# MDBU020.net
KiCad netlist of a schematic drawn in Altium Designer
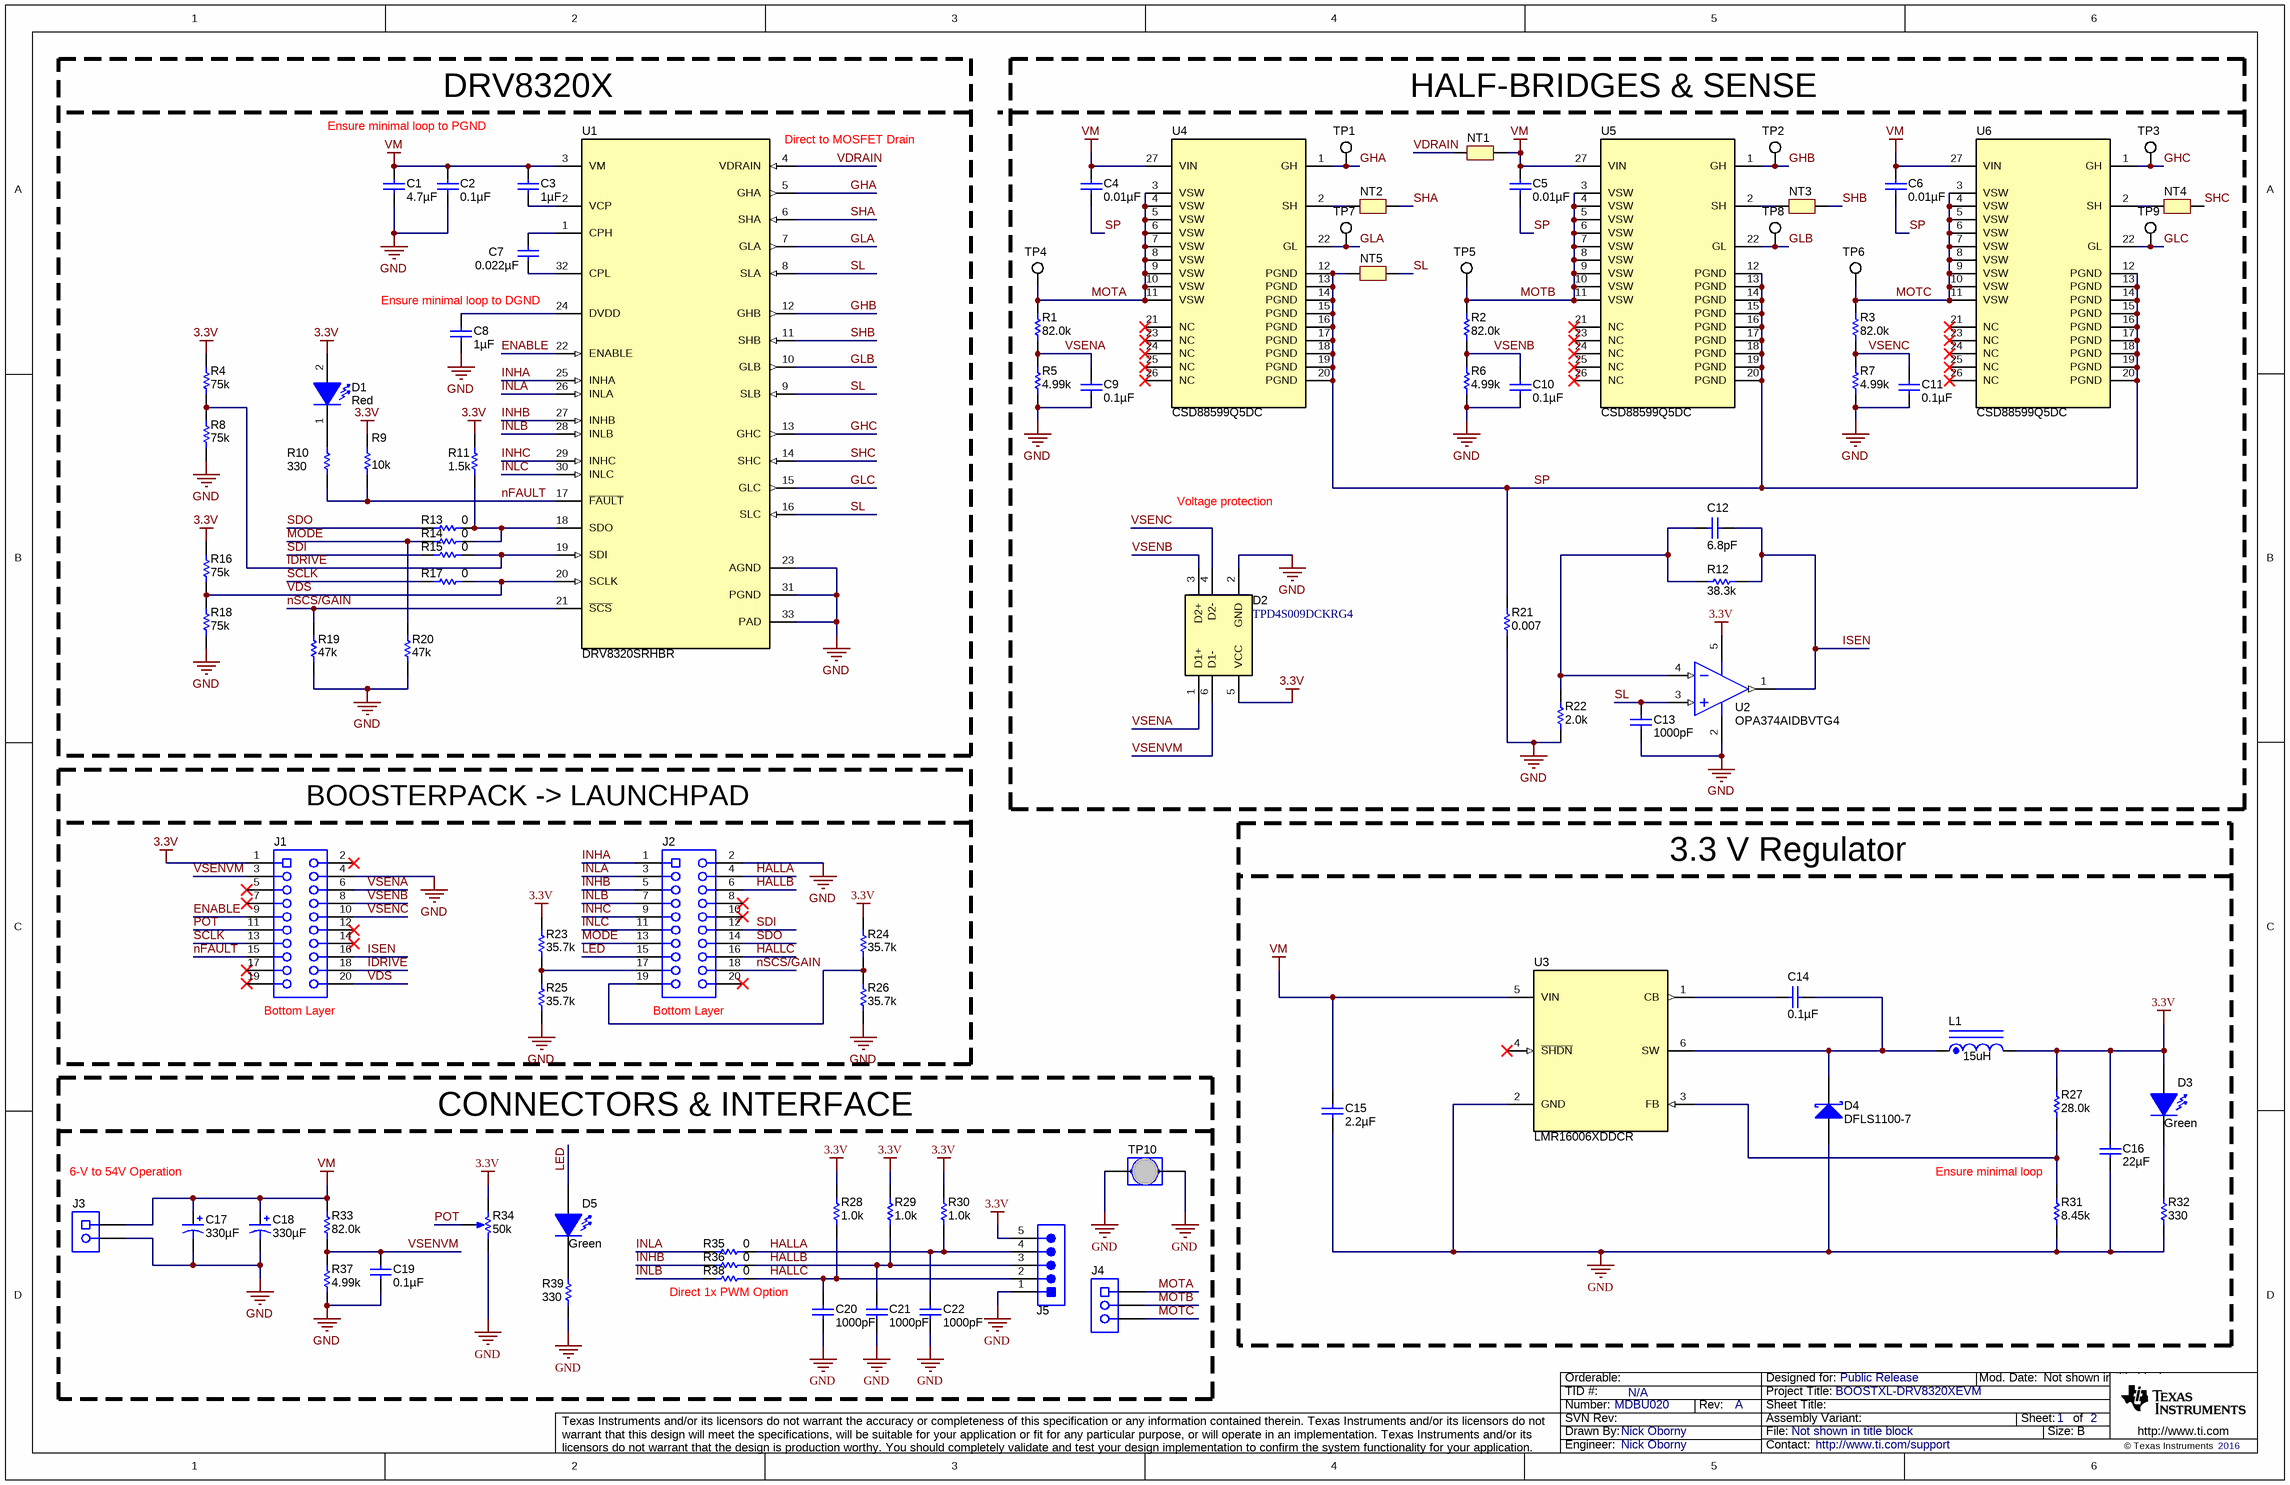
[diagram p0: MDBU020.SchDoc]

(export (version "E")
  (design (tool "Eeschema 10.0.6"))
  (components
    (comp (ref "C1")
      (value "CGA6M3X7S2A475K200AB")
      (footprint "1210_220L")
      (description "CAP, CERM, 4.7 µF, 100 V, +/- 10%, X7S, AEC-Q200 Grade 1, 1210")
      (fields
        (field (name "VALUEDISPLAYED") "4.7µF")
        (field (name "MANUFACTURER") "TDK")
        (field (name "PUBLISHER") "Texas Instruments")
      )
      (libsource (lib "Capacitor_Ceramic") (part "CGA6M3X7S2A475K200AB"))
    )
    (comp (ref "C2")
      (value "C1608X7S2A104K080AB")
      (footprint "0603L")
      (description "CAP, CERM, 0.1 µF, 100 V, +/- 10%, X7S, 0603")
      (fields
        (field (name "VALUEDISPLAYED") "0.1µF")
        (field (name "MANUFACTURER") "TDK")
        (field (name "PUBLISHER") "Texas Instruments")
      )
      (libsource (lib "Capacitor_Ceramic") (part "C1608X7S2A104K080AB"))
    )
    (comp (ref "C3")
      (value "GRM188R71C105KA12D")
      (footprint "0603L")
      (description "CAP, CERM, 1 µF, 16 V, +/- 10%, X7R, 0603")
      (fields
        (field (name "VALUEDISPLAYED") "1µF")
        (field (name "MANUFACTURER") "MuRata")
        (field (name "PUBLISHER") "Texas Instruments")
      )
      (libsource (lib "Capacitor_Ceramic") (part "GRM188R71C105KA12D"))
    )
    (comp (ref "C4")
      (value "GRM188R72A103KA01D")
      (footprint "0603L")
      (description "CAP, CERM, 0.01 µF, 100 V, +/- 10%, X7R, 0603")
      (fields
        (field (name "VALUEDISPLAYED") "0.01µF")
        (field (name "MANUFACTURER") "MuRata")
        (field (name "PUBLISHER") "Texas Instruments")
      )
      (libsource (lib "Capacitor_Ceramic") (part "GRM188R72A103KA01D"))
    )
    (comp (ref "C5")
      (value "GRM188R72A103KA01D")
      (footprint "0603L")
      (description "CAP, CERM, 0.01 µF, 100 V, +/- 10%, X7R, 0603")
      (fields
        (field (name "VALUEDISPLAYED") "0.01µF")
        (field (name "MANUFACTURER") "MuRata")
        (field (name "PUBLISHER") "Texas Instruments")
      )
      (libsource (lib "Capacitor_Ceramic") (part "GRM188R72A103KA01D"))
    )
    (comp (ref "C6")
      (value "GRM188R72A103KA01D")
      (footprint "0603L")
      (description "CAP, CERM, 0.01 µF, 100 V, +/- 10%, X7R, 0603")
      (fields
        (field (name "VALUEDISPLAYED") "0.01µF")
        (field (name "MANUFACTURER") "MuRata")
        (field (name "PUBLISHER") "Texas Instruments")
      )
      (libsource (lib "Capacitor_Ceramic") (part "GRM188R72A103KA01D"))
    )
    (comp (ref "C7")
      (value "C1608X7R2A223K")
      (footprint "0603L")
      (description "CAP, CERM, 0.022 µF, 100 V, +/- 10%, X7R, 0603")
      (fields
        (field (name "VALUEDISPLAYED") "0.022µF")
        (field (name "MANUFACTURER") "TDK")
        (field (name "PUBLISHER") "Texas Instruments")
      )
      (libsource (lib "Capacitor_Ceramic") (part "C1608X7R2A223K"))
    )
    (comp (ref "C8")
      (value "GRM188R70J105KA01D")
      (footprint "0603L")
      (description "CAP, CERM, 1 µF, 6.3 V, +/- 10%, X7R, 0603")
      (fields
        (field (name "VALUEDISPLAYED") "1µF")
        (field (name "MANUFACTURER") "MuRata")
        (field (name "PUBLISHER") "Texas Instruments")
      )
      (libsource (lib "Capacitor_Ceramic") (part "GRM188R70J105KA01D"))
    )
    (comp (ref "C9")
      (value "GRM188R71C104KA01D")
      (footprint "0603L")
      (description "CAP, CERM, 0.1 µF, 16 V, +/- 10%, X7R, 0603")
      (fields
        (field (name "VALUEDISPLAYED") "0.1µF")
        (field (name "MANUFACTURER") "MuRata")
        (field (name "PUBLISHER") "Texas Instruments")
      )
      (libsource (lib "Capacitor_Ceramic") (part "GRM188R71C104KA01D"))
    )
    (comp (ref "C10")
      (value "GRM188R71C104KA01D")
      (footprint "0603L")
      (description "CAP, CERM, 0.1 µF, 16 V, +/- 10%, X7R, 0603")
      (fields
        (field (name "VALUEDISPLAYED") "0.1µF")
        (field (name "MANUFACTURER") "MuRata")
        (field (name "PUBLISHER") "Texas Instruments")
      )
      (libsource (lib "Capacitor_Ceramic") (part "GRM188R71C104KA01D"))
    )
    (comp (ref "C11")
      (value "GRM188R71C104KA01D")
      (footprint "0603L")
      (description "CAP, CERM, 0.1 µF, 16 V, +/- 10%, X7R, 0603")
      (fields
        (field (name "VALUEDISPLAYED") "0.1µF")
        (field (name "MANUFACTURER") "MuRata")
        (field (name "PUBLISHER") "Texas Instruments")
      )
      (libsource (lib "Capacitor_Ceramic") (part "GRM188R71C104KA01D"))
    )
    (comp (ref "C12")
      (value "06035A6R8CAT2A")
      (footprint "0603L")
      (description "CAP, CERM, 6.8 pF, 50 V, +/- 4%, C0G/NP0, 0603")
      (fields
        (field (name "VALUEDISPLAYED") "6.8pF")
        (field (name "MANUFACTURER") "AVX")
        (field (name "PUBLISHER") "Texas Instruments")
      )
      (libsource (lib "Capacitor_Ceramic") (part "06035A6R8CAT2A"))
    )
    (comp (ref "C13")
      (value "885012206034")
      (footprint "0603L")
      (description "CAP, CERM, 1000 pF, 16 V, +/- 10%, X7R, 0603")
      (fields
        (field (name "VALUEDISPLAYED") "1000pF")
        (field (name "MANUFACTURER") "Wurth Elektronik")
        (field (name "PUBLISHER") "Texas Instruments")
      )
      (libsource (lib "Capacitor_Ceramic") (part "885012206034"))
    )
    (comp (ref "C14")
      (value "0603YC104JAT2A")
      (footprint "0603L")
      (description "CAP, CERM, 0.1 µF, 16 V, +/- 5%, X7R, 0603")
      (fields
        (field (name "VALUEDISPLAYED") "0.1µF")
        (field (name "MANUFACTURER") "AVX")
        (field (name "PUBLISHER") "Texas Instruments")
      )
      (libsource (lib "Capacitor_Ceramic") (part "0603YC104JAT2A"))
    )
    (comp (ref "C15")
      (value "GRM32ER72A225KA35L")
      (footprint "1210_220L")
      (description "CAP, CERM, 2.2 µF, 100 V, +/- 10%, X7R, 1210")
      (fields
        (field (name "VALUEDISPLAYED") "2.2µF")
        (field (name "MANUFACTURER") "MuRata")
        (field (name "PUBLISHER") "Texas Instruments")
      )
      (libsource (lib "Capacitor_Ceramic") (part "GRM32ER72A225KA35L"))
    )
    (comp (ref "C16")
      (value "GRM31CR61A226KE19L")
      (footprint "1206_180L")
      (description "CAP, CERM, 22 µF, 10 V, +/- 10%, X5R, 1206")
      (fields
        (field (name "VALUEDISPLAYED") "22µF")
        (field (name "MANUFACTURER") "MuRata")
        (field (name "PUBLISHER") "Texas Instruments")
      )
      (libsource (lib "Capacitor_Ceramic") (part "GRM31CR61A226KE19L"))
    )
    (comp (ref "C17")
      (value "EMVA630ADA331MKG5S")
      (footprint "CAPSMT_62_KG5")
      (description "CAP, AL, 330 µF, 63 V, +/- 20%, SMD")
      (fields
        (field (name "VALUEDISPLAYED") "330µF")
        (field (name "MANUFACTURER") "Chemi-Con")
        (field (name "PUBLISHER") "Texas Instruments")
      )
      (libsource (lib "Capacitor_Aluminum") (part "EMVA630ADA331MKG5S"))
    )
    (comp (ref "C18")
      (value "EMVA630ADA331MKG5S")
      (footprint "CAPSMT_62_KG5")
      (description "CAP, AL, 330 µF, 63 V, +/- 20%, SMD")
      (fields
        (field (name "VALUEDISPLAYED") "330µF")
        (field (name "MANUFACTURER") "Chemi-Con")
        (field (name "PUBLISHER") "Texas Instruments")
      )
      (libsource (lib "Capacitor_Aluminum") (part "EMVA630ADA331MKG5S"))
    )
    (comp (ref "C19")
      (value "C0603C104K4RACTU")
      (footprint "0603L")
      (description "CAP, CERM, 0.1 µF, 16 V, +/- 10%, X7R, 0603")
      (fields
        (field (name "VALUEDISPLAYED") "0.1µF")
        (field (name "MANUFACTURER") "Kemet")
        (field (name "PUBLISHER") "Texas Instruments")
      )
      (libsource (lib "Capacitor_Ceramic") (part "C0603C104K4RACTU"))
    )
    (comp (ref "C20")
      (value "885012206034")
      (footprint "0603L")
      (description "CAP, CERM, 1000 pF, 16 V, +/- 10%, X7R, 0603")
      (fields
        (field (name "VALUEDISPLAYED") "1000pF")
        (field (name "MANUFACTURER") "Wurth Elektronik")
        (field (name "PUBLISHER") "Texas Instruments")
      )
      (libsource (lib "Capacitor_Ceramic") (part "885012206034"))
    )
    (comp (ref "C21")
      (value "885012206034")
      (footprint "0603L")
      (description "CAP, CERM, 1000 pF, 16 V, +/- 10%, X7R, 0603")
      (fields
        (field (name "VALUEDISPLAYED") "1000pF")
        (field (name "MANUFACTURER") "Wurth Elektronik")
        (field (name "PUBLISHER") "Texas Instruments")
      )
      (libsource (lib "Capacitor_Ceramic") (part "885012206034"))
    )
    (comp (ref "C22")
      (value "885012206034")
      (footprint "0603L")
      (description "CAP, CERM, 1000 pF, 16 V, +/- 10%, X7R, 0603")
      (fields
        (field (name "VALUEDISPLAYED") "1000pF")
        (field (name "MANUFACTURER") "Wurth Elektronik")
        (field (name "PUBLISHER") "Texas Instruments")
      )
      (libsource (lib "Capacitor_Ceramic") (part "885012206034"))
    )
    (comp (ref "D1")
      (value "Red")
      (footprint "WL-SMCW_RED")
      (description "LED, Red, SMD")
      (fields
        (field (name "MANUFACTURER") "Wurth Elektronik")
        (field (name "PARTNUMBER") "150060RS75000")
        (field (name "PUBLISHER") "Texas Instruments")
      )
      (libsource (lib "LED") (part "150060RS75000"))
    )
    (comp (ref "D2")
      (value "TPD4S009DCKRG4")
      (footprint "DCK0006A_L")
      (fields
        (field (name "MANUFACTURER") "Texas Instruments")
        (field (name "ALTERNATE PARTNUMBER") "Equivalent")
      )
      (libsource (lib "TI Interface ESD EMI Protection") (part "TPD4S009DCKRG4"))
    )
    (comp (ref "D3")
      (value "Green")
      (footprint "LED_LTST-C171")
      (description "LED, Green, SMD")
      (fields
        (field (name "MANUFACTURER") "Lite-On")
        (field (name "PARTNUMBER") "LTST-C171GKT")
        (field (name "PUBLISHER") "Texas Instruments")
      )
      (libsource (lib "LED") (part "LTST-C171GKT"))
    )
    (comp (ref "D4")
      (value "DFLS1100-7")
      (footprint "PowerDI123")
      (description "Diode, Schottky, 100 V, 1 A, PowerDI123")
      (fields (field (name "MANUFACTURER") "Diodes Inc.") (field (name "PUBLISHER") "Texas Instruments"))
      (libsource (lib "Diode") (part "DFLS1100-7"))
    )
    (comp (ref "D5")
      (value "Green")
      (footprint "LED_LTST-C171")
      (description "LED, Green, SMD")
      (fields
        (field (name "MANUFACTURER") "Lite-On")
        (field (name "PARTNUMBER") "LTST-C171GKT")
        (field (name "PUBLISHER") "Texas Instruments")
      )
      (libsource (lib "LED") (part "LTST-C171GKT"))
    )
    (comp (ref "J1")
      (value "SSQ-110-03-G-D")
      (footprint "Samtec_SSQ-110-03-x-D")
      (description "Receptacle, 2.54mm, 10x2, Gold, TH")
      (fields
        (field (name "MANUFACTURER") "Samtec")
        (field (name "SYMBOLCREATOR") "a0412235")
        (field (name "PUBLISHER") "Texas Instruments")
      )
      (libsource (lib "Connectors_Samtec") (part "SSQ-110-03-G-D"))
    )
    (comp (ref "J2")
      (value "SSQ-110-03-G-D")
      (footprint "Samtec_SSQ-110-03-x-D")
      (description "Receptacle, 2.54mm, 10x2, Gold, TH")
      (fields
        (field (name "MANUFACTURER") "Samtec")
        (field (name "SYMBOLCREATOR") "a0412235")
        (field (name "PUBLISHER") "Texas Instruments")
      )
      (libsource (lib "Connectors_Samtec") (part "SSQ-110-03-G-D"))
    )
    (comp (ref "J3")
      (value "691 101 710 002")
      (footprint "Wurth_691101710002")
      (description "Terminal Block, 5 mm, 2x1, Tin, TH")
      (fields
        (field (name "MANUFACTURER") "Wurth Elektronik eiSos")
        (field (name "SYMBOLCREATOR") "a0412235")
        (field (name "PUBLISHER") "Texas Instruments")
      )
      (libsource (lib "Connectors_Other") (part "691 101 710 002"))
    )
    (comp (ref "J4")
      (value "691 101 710 003")
      (footprint "Wurth_691101710003")
      (description "Terminal Block, 5 mm, 3x1, Tin, TH")
      (fields
        (field (name "MANUFACTURER") "Wurth Elektronik eiSos")
        (field (name "SYMBOLCREATOR") "a0412235")
        (field (name "PUBLISHER") "Texas Instruments")
      )
      (libsource (lib "Connectors_Other") (part "691 101 710 003"))
    )
    (comp (ref "J5")
      (value "PEC05SAAN")
      (footprint "Sullins_PxC05SAAN")
      (description "Header, 2.54mm, 5x1, Tin, TH")
      (fields
        (field (name "MANUFACTURER") "Sullins Connector Solutions")
        (field (name "SYMBOLCREATOR") "a0412235")
        (field (name "PUBLISHER") "Texas Instruments")
      )
      (libsource (lib "Connectors_Sullins") (part "PEC05SAAN"))
    )
    (comp (ref "L1")
      (value "15uH")
      (footprint "SD53")
      (description "Inductor, Shielded Drum Core, Ferrite, 15 µH, 1.1 A, 0.122 ohm, SMD")
      (fields
        (field (name "PARTNUMBER") "SD53-150-R")
        (field (name "MANUFACTURER") "Cooper Bussman")
        (field (name "SYMBOLCREATOR") "a0412235")
        (field (name "PUBLISHER") "Texas Instruments")
      )
      (libsource (lib "Inductor_Other") (part "SD53-150-R"))
    )
    (comp (ref "NT1")
      (value "Net-Tie")
      (footprint "Net-Tie_10mil")
      (description "Single point connection between nets.")
      (fields (field (name "SYMBOLCREATOR") "codlsc") (field (name "PUBLISHER") "Texas Instruments"))
      (libsource (lib "MiscParts") (part "Net-Tie"))
    )
    (comp (ref "NT2")
      (value "Net-Tie")
      (footprint "Net-Tie_10mil")
      (description "Single point connection between nets.")
      (fields (field (name "SYMBOLCREATOR") "codlsc") (field (name "PUBLISHER") "Texas Instruments"))
      (libsource (lib "MiscParts") (part "Net-Tie"))
    )
    (comp (ref "NT3")
      (value "Net-Tie")
      (footprint "Net-Tie_10mil")
      (description "Single point connection between nets.")
      (fields (field (name "SYMBOLCREATOR") "codlsc") (field (name "PUBLISHER") "Texas Instruments"))
      (libsource (lib "MiscParts") (part "Net-Tie"))
    )
    (comp (ref "NT4")
      (value "Net-Tie")
      (footprint "Net-Tie_10mil")
      (description "Single point connection between nets.")
      (fields (field (name "SYMBOLCREATOR") "codlsc") (field (name "PUBLISHER") "Texas Instruments"))
      (libsource (lib "MiscParts") (part "Net-Tie"))
    )
    (comp (ref "NT5")
      (value "Net-Tie")
      (footprint "Net-Tie_10mil")
      (description "Single point connection between nets.")
      (fields (field (name "SYMBOLCREATOR") "codlsc") (field (name "PUBLISHER") "Texas Instruments"))
      (libsource (lib "MiscParts") (part "Net-Tie"))
    )
    (comp (ref "R1")
      (value "RC0603FR-0782KL")
      (footprint "0603L")
      (description "RES, 82.0 k, 1%, 0.1 W, 0603")
      (fields
        (field (name "VALUEDISPLAYED") "82.0k")
        (field (name "MANUFACTURER") "Yageo America")
        (field (name "PUBLISHER") "Texas Instruments")
      )
      (libsource (lib "Resistor_0603") (part "RC0603FR-0782KL"))
    )
    (comp (ref "R2")
      (value "RC0603FR-0782KL")
      (footprint "0603L")
      (description "RES, 82.0 k, 1%, 0.1 W, 0603")
      (fields
        (field (name "VALUEDISPLAYED") "82.0k")
        (field (name "MANUFACTURER") "Yageo America")
        (field (name "PUBLISHER") "Texas Instruments")
      )
      (libsource (lib "Resistor_0603") (part "RC0603FR-0782KL"))
    )
    (comp (ref "R3")
      (value "RC0603FR-0782KL")
      (footprint "0603L")
      (description "RES, 82.0 k, 1%, 0.1 W, 0603")
      (fields
        (field (name "VALUEDISPLAYED") "82.0k")
        (field (name "MANUFACTURER") "Yageo America")
        (field (name "PUBLISHER") "Texas Instruments")
      )
      (libsource (lib "Resistor_0603") (part "RC0603FR-0782KL"))
    )
    (comp (ref "R4")
      (value "CRCW060375K0JNEA")
      (footprint "0603L")
      (description "RES, 75 k, 5%, 0.1 W, 0603")
      (fields
        (field (name "VALUEDISPLAYED") "75k")
        (field (name "MANUFACTURER") "Vishay-Dale")
        (field (name "PUBLISHER") "Texas Instruments")
      )
      (libsource (lib "Resistor_0603") (part "CRCW060375K0JNEA"))
    )
    (comp (ref "R5")
      (value "RC0603FR-074K99L")
      (footprint "0603L")
      (description "RES, 4.99 k, 1%, 0.1 W, 0603")
      (fields
        (field (name "VALUEDISPLAYED") "4.99k")
        (field (name "MANUFACTURER") "Yageo America")
        (field (name "PUBLISHER") "Texas Instruments")
      )
      (libsource (lib "Resistor_0603") (part "RC0603FR-074K99L"))
    )
    (comp (ref "R6")
      (value "RC0603FR-074K99L")
      (footprint "0603L")
      (description "RES, 4.99 k, 1%, 0.1 W, 0603")
      (fields
        (field (name "VALUEDISPLAYED") "4.99k")
        (field (name "MANUFACTURER") "Yageo America")
        (field (name "PUBLISHER") "Texas Instruments")
      )
      (libsource (lib "Resistor_0603") (part "RC0603FR-074K99L"))
    )
    (comp (ref "R7")
      (value "RC0603FR-074K99L")
      (footprint "0603L")
      (description "RES, 4.99 k, 1%, 0.1 W, 0603")
      (fields
        (field (name "VALUEDISPLAYED") "4.99k")
        (field (name "MANUFACTURER") "Yageo America")
        (field (name "PUBLISHER") "Texas Instruments")
      )
      (libsource (lib "Resistor_0603") (part "RC0603FR-074K99L"))
    )
    (comp (ref "R8")
      (value "CRCW060375K0JNEA")
      (footprint "0603L")
      (description "RES, 75 k, 5%, 0.1 W, 0603")
      (fields
        (field (name "VALUEDISPLAYED") "75k")
        (field (name "MANUFACTURER") "Vishay-Dale")
        (field (name "PUBLISHER") "Texas Instruments")
      )
      (libsource (lib "Resistor_0603") (part "CRCW060375K0JNEA"))
    )
    (comp (ref "R9")
      (value "CRCW060310K0JNEA")
      (footprint "0603L")
      (description "RES, 10 k, 5%, 0.1 W, 0603")
      (fields
        (field (name "VALUEDISPLAYED") "10k")
        (field (name "MANUFACTURER") "Vishay-Dale")
        (field (name "PUBLISHER") "Texas Instruments")
      )
      (libsource (lib "Resistor_0603") (part "CRCW060310K0JNEA"))
    )
    (comp (ref "R10")
      (value "330")
      (footprint "0603L")
      (description "RES, 330 ohm, 5%, 0.1W, 0603")
      (fields
        (field (name "PARTNUMBER") "CRCW0603330RJNEA")
        (field (name "MANUFACTURER") "Vishay-Dale")
        (field (name "PUBLISHER") "Texas Instruments")
      )
      (libsource (lib "Resistor_0603") (part "CRCW0603330RJNEA"))
    )
    (comp (ref "R11")
      (value "CRCW06031K50JNEA")
      (footprint "0603L")
      (description "RES, 1.5 k, 5%, 0.1 W, 0603")
      (fields
        (field (name "VALUEDISPLAYED") "1.5k")
        (field (name "MANUFACTURER") "Vishay-Dale")
        (field (name "PUBLISHER") "Texas Instruments")
      )
      (libsource (lib "Resistor_0603") (part "CRCW06031K50JNEA"))
    )
    (comp (ref "R12")
      (value "CRCW060338K3FKEA")
      (footprint "0603L")
      (description "RES, 38.3 k, 1%, 0.1 W, 0603")
      (fields
        (field (name "VALUEDISPLAYED") "38.3k")
        (field (name "MANUFACTURER") "Vishay-Dale")
        (field (name "PUBLISHER") "Texas Instruments")
      )
      (libsource (lib "Resistor_0603") (part "CRCW060338K3FKEA"))
    )
    (comp (ref "R13")
      (value "0")
      (footprint "0603L")
      (description "RES, 0, 5%, 0.1 W, 0603")
      (fields
        (field (name "PARTNUMBER") "CRCW06030000Z0EA")
        (field (name "MANUFACTURER") "Vishay-Dale")
        (field (name "PUBLISHER") "Texas Instruments")
      )
      (libsource (lib "Resistor_0603") (part "CRCW06030000Z0EA"))
    )
    (comp (ref "R14")
      (value "0")
      (footprint "0603L")
      (description "RES, 0, 5%, 0.1 W, 0603")
      (fields
        (field (name "PARTNUMBER") "CRCW06030000Z0EA")
        (field (name "MANUFACTURER") "Vishay-Dale")
        (field (name "PUBLISHER") "Texas Instruments")
      )
      (libsource (lib "Resistor_0603") (part "CRCW06030000Z0EA"))
    )
    (comp (ref "R15")
      (value "0")
      (footprint "0603L")
      (description "RES, 0, 5%, 0.1 W, 0603")
      (fields
        (field (name "PARTNUMBER") "CRCW06030000Z0EA")
        (field (name "MANUFACTURER") "Vishay-Dale")
        (field (name "PUBLISHER") "Texas Instruments")
      )
      (libsource (lib "Resistor_0603") (part "CRCW06030000Z0EA"))
    )
    (comp (ref "R16")
      (value "CRCW060375K0JNEA")
      (footprint "0603L")
      (description "RES, 75 k, 5%, 0.1 W, 0603")
      (fields
        (field (name "VALUEDISPLAYED") "75k")
        (field (name "MANUFACTURER") "Vishay-Dale")
        (field (name "PUBLISHER") "Texas Instruments")
      )
      (libsource (lib "Resistor_0603") (part "CRCW060375K0JNEA"))
    )
    (comp (ref "R17")
      (value "0")
      (footprint "0603L")
      (description "RES, 0, 5%, 0.1 W, 0603")
      (fields
        (field (name "PARTNUMBER") "CRCW06030000Z0EA")
        (field (name "MANUFACTURER") "Vishay-Dale")
        (field (name "PUBLISHER") "Texas Instruments")
      )
      (libsource (lib "Resistor_0603") (part "CRCW06030000Z0EA"))
    )
    (comp (ref "R18")
      (value "CRCW060375K0JNEA")
      (footprint "0603L")
      (description "RES, 75 k, 5%, 0.1 W, 0603")
      (fields
        (field (name "VALUEDISPLAYED") "75k")
        (field (name "MANUFACTURER") "Vishay-Dale")
        (field (name "PUBLISHER") "Texas Instruments")
      )
      (libsource (lib "Resistor_0603") (part "CRCW060375K0JNEA"))
    )
    (comp (ref "R19")
      (value "CRCW060347K0JNEA")
      (footprint "0603L")
      (description "RES, 47 k, 5%, 0.1 W, 0603")
      (fields
        (field (name "VALUEDISPLAYED") "47k")
        (field (name "MANUFACTURER") "Vishay-Dale")
        (field (name "PUBLISHER") "Texas Instruments")
      )
      (libsource (lib "Resistor_0603") (part "CRCW060347K0JNEA"))
    )
    (comp (ref "R20")
      (value "CRCW060347K0JNEA")
      (footprint "0603L")
      (description "RES, 47 k, 5%, 0.1 W, 0603")
      (fields
        (field (name "VALUEDISPLAYED") "47k")
        (field (name "MANUFACTURER") "Vishay-Dale")
        (field (name "PUBLISHER") "Texas Instruments")
      )
      (libsource (lib "Resistor_0603") (part "CRCW060347K0JNEA"))
    )
    (comp (ref "R21")
      (value "CRE2512-FZ-R007E-3")
      (footprint "2512L")
      (description "RES SMD 0.007 OHM 1% 3W 2512")
      (fields
        (field (name "VALUEDISPLAYED") "0.007")
        (field (name "MANUFACTURER") "Bourns Inc.")
        (field (name "PUBLISHER") "Texas Instruments")
      )
      (libsource (lib "Resistor_2512") (part "PMR100HZPFU7L00"))
    )
    (comp (ref "R22")
      (value "CRCW06032K00JNEA")
      (footprint "0603L")
      (description "RES, 2.0 k, 5%, 0.1 W, 0603")
      (fields
        (field (name "VALUEDISPLAYED") "2.0k")
        (field (name "MANUFACTURER") "Vishay-Dale")
        (field (name "PUBLISHER") "Texas Instruments")
      )
      (libsource (lib "Resistor_0603") (part "CRCW06032K00JNEA"))
    )
    (comp (ref "R23")
      (value "RC0603FR-0735K7L")
      (footprint "0603L")
      (description "RES, 35.7 k, 1%, 0.1 W, 0603")
      (fields
        (field (name "VALUEDISPLAYED") "35.7k")
        (field (name "MANUFACTURER") "Yageo America")
        (field (name "PUBLISHER") "Texas Instruments")
      )
      (libsource (lib "Resistor_0603") (part "RC0603FR-0735K7L"))
    )
    (comp (ref "R24")
      (value "RC0603FR-0735K7L")
      (footprint "0603L")
      (description "RES, 35.7 k, 1%, 0.1 W, 0603")
      (fields
        (field (name "VALUEDISPLAYED") "35.7k")
        (field (name "MANUFACTURER") "Yageo America")
        (field (name "PUBLISHER") "Texas Instruments")
      )
      (libsource (lib "Resistor_0603") (part "RC0603FR-0735K7L"))
    )
    (comp (ref "R25")
      (value "RC0603FR-0735K7L")
      (footprint "0603L")
      (description "RES, 35.7 k, 1%, 0.1 W, 0603")
      (fields
        (field (name "VALUEDISPLAYED") "35.7k")
        (field (name "MANUFACTURER") "Yageo America")
        (field (name "PUBLISHER") "Texas Instruments")
      )
      (libsource (lib "Resistor_0603") (part "RC0603FR-0735K7L"))
    )
    (comp (ref "R26")
      (value "RC0603FR-0735K7L")
      (footprint "0603L")
      (description "RES, 35.7 k, 1%, 0.1 W, 0603")
      (fields
        (field (name "VALUEDISPLAYED") "35.7k")
        (field (name "MANUFACTURER") "Yageo America")
        (field (name "PUBLISHER") "Texas Instruments")
      )
      (libsource (lib "Resistor_0603") (part "RC0603FR-0735K7L"))
    )
    (comp (ref "R27")
      (value "CRCW060328K0FKEA")
      (footprint "0603L")
      (description "RES, 28.0 k, 1%, 0.1 W, 0603")
      (fields
        (field (name "VALUEDISPLAYED") "28.0k")
        (field (name "MANUFACTURER") "Vishay-Dale")
        (field (name "PUBLISHER") "Texas Instruments")
      )
      (libsource (lib "Resistor_0603") (part "CRCW060328K0FKEA"))
    )
    (comp (ref "R28")
      (value "CRCW06031K00JNEA")
      (footprint "0603L")
      (description "RES, 1.0 k, 5%, 0.1 W, 0603")
      (fields
        (field (name "VALUEDISPLAYED") "1.0k")
        (field (name "MANUFACTURER") "Vishay-Dale")
        (field (name "PUBLISHER") "Texas Instruments")
      )
      (libsource (lib "Resistor_0603") (part "CRCW06031K00JNEA"))
    )
    (comp (ref "R29")
      (value "CRCW06031K00JNEA")
      (footprint "0603L")
      (description "RES, 1.0 k, 5%, 0.1 W, 0603")
      (fields
        (field (name "VALUEDISPLAYED") "1.0k")
        (field (name "MANUFACTURER") "Vishay-Dale")
        (field (name "PUBLISHER") "Texas Instruments")
      )
      (libsource (lib "Resistor_0603") (part "CRCW06031K00JNEA"))
    )
    (comp (ref "R30")
      (value "CRCW06031K00JNEA")
      (footprint "0603L")
      (description "RES, 1.0 k, 5%, 0.1 W, 0603")
      (fields
        (field (name "VALUEDISPLAYED") "1.0k")
        (field (name "MANUFACTURER") "Vishay-Dale")
        (field (name "PUBLISHER") "Texas Instruments")
      )
      (libsource (lib "Resistor_0603") (part "CRCW06031K00JNEA"))
    )
    (comp (ref "R31")
      (value "CRCW06038K45FKEA")
      (footprint "0603L")
      (description "RES, 8.45 k, 1%, 0.1 W, 0603")
      (fields
        (field (name "VALUEDISPLAYED") "8.45k")
        (field (name "MANUFACTURER") "Vishay-Dale")
        (field (name "PUBLISHER") "Texas Instruments")
      )
      (libsource (lib "Resistor_0603") (part "CRCW06038K45FKEA"))
    )
    (comp (ref "R32")
      (value "RC0603JR-07330RL")
      (footprint "0603L")
      (description "RES, 330, 5%, 0.1 W, 0603")
      (fields
        (field (name "VALUEDISPLAYED") "330")
        (field (name "MANUFACTURER") "Yageo America")
        (field (name "PUBLISHER") "Texas Instruments")
      )
      (libsource (lib "Resistor_0603") (part "RC0603JR-07330RL"))
    )
    (comp (ref "R33")
      (value "RC0603FR-0782KL")
      (footprint "0603L")
      (description "RES, 82.0 k, 1%, 0.1 W, 0603")
      (fields
        (field (name "VALUEDISPLAYED") "82.0k")
        (field (name "MANUFACTURER") "Yageo America")
        (field (name "PUBLISHER") "Texas Instruments")
      )
      (libsource (lib "Resistor_0603") (part "RC0603FR-0782KL"))
    )
    (comp (ref "R34")
      (value "50k")
      (footprint "Bourns_3352T")
      (description "Trimming Potentiometer, 50K, 0.5W, TH")
      (fields
        (field (name "PARTNUMBER") "3352T-1-503LF")
        (field (name "MANUFACTURER") "Bourns")
        (field (name "SYMBOLCREATOR") "a0412235")
        (field (name "PUBLISHER") "Texas Instruments")
      )
      (libsource (lib "Other_Passive") (part "3352T-1-503LF"))
    )
    (comp (ref "R35")
      (value "0")
      (footprint "0603L")
      (description "RES, 0, 5%, 0.1 W, 0603")
      (fields
        (field (name "PARTNUMBER") "CRCW06030000Z0EA")
        (field (name "MANUFACTURER") "Vishay-Dale")
        (field (name "PUBLISHER") "Texas Instruments")
      )
      (libsource (lib "Resistor_0603") (part "CRCW06030000Z0EA"))
    )
    (comp (ref "R36")
      (value "0")
      (footprint "0603L")
      (description "RES, 0, 5%, 0.1 W, 0603")
      (fields
        (field (name "PARTNUMBER") "CRCW06030000Z0EA")
        (field (name "MANUFACTURER") "Vishay-Dale")
        (field (name "PUBLISHER") "Texas Instruments")
      )
      (libsource (lib "Resistor_0603") (part "CRCW06030000Z0EA"))
    )
    (comp (ref "R37")
      (value "RC0603FR-074K99L")
      (footprint "0603L")
      (description "RES, 4.99 k, 1%, 0.1 W, 0603")
      (fields
        (field (name "VALUEDISPLAYED") "4.99k")
        (field (name "MANUFACTURER") "Yageo America")
        (field (name "PUBLISHER") "Texas Instruments")
      )
      (libsource (lib "Resistor_0603") (part "RC0603FR-074K99L"))
    )
    (comp (ref "R38")
      (value "0")
      (footprint "0603L")
      (description "RES, 0, 5%, 0.1 W, 0603")
      (fields
        (field (name "PARTNUMBER") "CRCW06030000Z0EA")
        (field (name "MANUFACTURER") "Vishay-Dale")
        (field (name "PUBLISHER") "Texas Instruments")
      )
      (libsource (lib "Resistor_0603") (part "CRCW06030000Z0EA"))
    )
    (comp (ref "R39")
      (value "330")
      (footprint "0603L")
      (description "RES, 330, 5%, 0.1 W, 0603")
      (fields
        (field (name "PARTNUMBER") "CRCW0603330RJNEA")
        (field (name "MANUFACTURER") "Vishay-Dale")
        (field (name "PUBLISHER") "Texas Instruments")
      )
      (libsource (lib "Resistor_0603") (part "CRCW0603330RJNEA"))
    )
    (comp (ref "TP1")
      (value "5002")
      (footprint "Keystone5002")
      (description "Test Point, Miniature, White, TH")
      (fields (field (name "MANUFACTURER") "Keystone") (field (name "PUBLISHER") "Texas Instruments"))
      (libsource (lib "Connectors_Keystone") (part "5002"))
    )
    (comp (ref "TP2")
      (value "5002")
      (footprint "Keystone5002")
      (description "Test Point, Miniature, White, TH")
      (fields (field (name "MANUFACTURER") "Keystone") (field (name "PUBLISHER") "Texas Instruments"))
      (libsource (lib "Connectors_Keystone") (part "5002"))
    )
    (comp (ref "TP3")
      (value "5002")
      (footprint "Keystone5002")
      (description "Test Point, Miniature, White, TH")
      (fields (field (name "MANUFACTURER") "Keystone") (field (name "PUBLISHER") "Texas Instruments"))
      (libsource (lib "Connectors_Keystone") (part "5002"))
    )
    (comp (ref "TP4")
      (value "5002")
      (footprint "Keystone5002")
      (description "Test Point, Miniature, White, TH")
      (fields (field (name "MANUFACTURER") "Keystone") (field (name "PUBLISHER") "Texas Instruments"))
      (libsource (lib "Connectors_Keystone") (part "5002"))
    )
    (comp (ref "TP5")
      (value "5002")
      (footprint "Keystone5002")
      (description "Test Point, Miniature, White, TH")
      (fields (field (name "MANUFACTURER") "Keystone") (field (name "PUBLISHER") "Texas Instruments"))
      (libsource (lib "Connectors_Keystone") (part "5002"))
    )
    (comp (ref "TP6")
      (value "5002")
      (footprint "Keystone5002")
      (description "Test Point, Miniature, White, TH")
      (fields (field (name "MANUFACTURER") "Keystone") (field (name "PUBLISHER") "Texas Instruments"))
      (libsource (lib "Connectors_Keystone") (part "5002"))
    )
    (comp (ref "TP7")
      (value "5002")
      (footprint "Keystone5002")
      (description "Test Point, Miniature, White, TH")
      (fields (field (name "MANUFACTURER") "Keystone") (field (name "PUBLISHER") "Texas Instruments"))
      (libsource (lib "Connectors_Keystone") (part "5002"))
    )
    (comp (ref "TP8")
      (value "5002")
      (footprint "Keystone5002")
      (description "Test Point, Miniature, White, TH")
      (fields (field (name "MANUFACTURER") "Keystone") (field (name "PUBLISHER") "Texas Instruments"))
      (libsource (lib "Connectors_Keystone") (part "5002"))
    )
    (comp (ref "TP9")
      (value "5002")
      (footprint "Keystone5002")
      (description "Test Point, Miniature, White, TH")
      (fields (field (name "MANUFACTURER") "Keystone") (field (name "PUBLISHER") "Texas Instruments"))
      (libsource (lib "Connectors_Keystone") (part "5002"))
    )
    (comp (ref "TP10")
      (value "D3082-05")
      (footprint "Harwin_D3082-05")
      (description "1mm Uninsulated Shorting Plug, 10.16mm spacing, TH")
      (fields
        (field (name "MANUFACTURER") "Harwin")
        (field (name "SYMBOLCREATOR") "a0799628")
        (field (name "PUBLISHER") "Texas Instruments")
      )
      (libsource (lib "Connectors_Other") (part "D3082-05"))
    )
    (comp (ref "U1")
      (value "DRV8320SRHBR")
      (footprint "RHB0032E")
      (description "60-V Three-Phase Smart Gate Driver, RHB0032E")
      (fields
        (field (name "ALTERNATE PARTNUMBER") "DRV8320SRHBT")
        (field (name "MANUFACTURER") "Texas Instruments")
        (field (name "SYMBOLCREATOR") "Altium")
        (field (name "PUBLISHER") "Texas Instruments")
      )
      (libsource (lib "TI_Pre_RTM") (part "DRV8320SRHBR"))
    )
    (comp (ref "U2")
      (value "OPA374AIDBVTG4")
      (footprint "DBV0005A_L")
      (fields
        (field (name "MANUFACTURER") "Texas Instruments")
        (field (name "ALTERNATE PARTNUMBER") "Equivalent")
      )
      (libsource (lib "TI Amplifiers and Linear Operational Amplifier Precision Amplifier Part One") (part "OPA374AIDBVTG4"))
    )
    (comp (ref "U3")
      (value "LMR16006XDDCR")
      (footprint "DDC0006A_L")
      (description "Wide Input Voltage Range Buck Regulator with High Efficiency Sleep Mode, DDC0006A")
      (fields
        (field (name "ALTERNATE PARTNUMBER") "LMR16006XDDCT")
        (field (name "MANUFACTURER") "Texas Instruments")
        (field (name "SYMBOLCREATOR") "x0208326")
        (field (name "PUBLISHER") "Texas Instruments")
      )
      (libsource (lib "TI_Pre_Release") (part "LMR16006XDDCR"))
    )
    (comp (ref "U4")
      (value "CSD88599Q5DC")
      (footprint "DMM0022A")
      (description "60 V Half-Bridge NexFE Power Block, DMM0022A (LSON-CLIP-27)")
      (fields
        (field (name "ALTERNATE PARTNUMBER") "CSD88599Q5DCT")
        (field (name "MANUFACTURER") "Texas Instruments")
        (field (name "SYMBOLCREATOR") "Altium")
        (field (name "PUBLISHER") "Texas Instruments")
      )
      (libsource (lib "TI_Pre_RTM") (part "CSD88599Q5DC"))
    )
    (comp (ref "U5")
      (value "CSD88599Q5DC")
      (footprint "DMM0022A")
      (description "60 V Half-Bridge NexFE Power Block, DMM0022A (LSON-CLIP-27)")
      (fields
        (field (name "ALTERNATE PARTNUMBER") "CSD88599Q5DCT")
        (field (name "MANUFACTURER") "Texas Instruments")
        (field (name "SYMBOLCREATOR") "Altium")
        (field (name "PUBLISHER") "Texas Instruments")
      )
      (libsource (lib "TI_Pre_RTM") (part "CSD88599Q5DC"))
    )
    (comp (ref "U6")
      (value "CSD88599Q5DC")
      (footprint "DMM0022A")
      (description "60 V Half-Bridge NexFE Power Block, DMM0022A (LSON-CLIP-27)")
      (fields
        (field (name "ALTERNATE PARTNUMBER") "CSD88599Q5DCT")
        (field (name "MANUFACTURER") "Texas Instruments")
        (field (name "SYMBOLCREATOR") "Altium")
        (field (name "PUBLISHER") "Texas Instruments")
      )
      (libsource (lib "TI_Pre_RTM") (part "CSD88599Q5DC"))
    )
  )
  (nets
    (net (code "1") (name "/ENABLE") (class "Default")
      (node (ref "J1") (pin "9") (pinfunction "9_9") (pintype "passive"))
      (node (ref "U1") (pin "22") (pinfunction "ENABLE_22") (pintype "input"))
    )
    (net (code "2") (name "/GHA") (class "Default")
      (node (ref "TP1") (pin "1") (pintype "passive"))
      (node (ref "U1") (pin "5") (pinfunction "GHA_5") (pintype "output"))
      (node (ref "U4") (pin "1") (pinfunction "GH_1") (pintype "passive"))
    )
    (net (code "3") (name "/GHB") (class "Default")
      (node (ref "TP2") (pin "1") (pintype "passive"))
      (node (ref "U1") (pin "12") (pinfunction "GHB_12") (pintype "output"))
      (node (ref "U5") (pin "1") (pinfunction "GH_1") (pintype "passive"))
    )
    (net (code "4") (name "/GHC") (class "Default")
      (node (ref "TP3") (pin "1") (pintype "passive"))
      (node (ref "U1") (pin "13") (pinfunction "GHC_13") (pintype "output"))
      (node (ref "U6") (pin "1") (pinfunction "GH_1") (pintype "passive"))
    )
    (net (code "5") (name "/GLA") (class "Default")
      (node (ref "TP7") (pin "1") (pintype "passive"))
      (node (ref "U1") (pin "7") (pinfunction "GLA_7") (pintype "output"))
      (node (ref "U4") (pin "22") (pinfunction "GL_22") (pintype "passive"))
    )
    (net (code "6") (name "/GLB") (class "Default")
      (node (ref "TP8") (pin "1") (pintype "passive"))
      (node (ref "U1") (pin "10") (pinfunction "GLB_10") (pintype "output"))
      (node (ref "U5") (pin "22") (pinfunction "GL_22") (pintype "passive"))
    )
    (net (code "7") (name "/GLC") (class "Default")
      (node (ref "TP9") (pin "1") (pintype "passive"))
      (node (ref "U1") (pin "15") (pinfunction "GLC_15") (pintype "output"))
      (node (ref "U6") (pin "22") (pinfunction "GL_22") (pintype "passive"))
    )
    (net (code "8") (name "/HALLA") (class "Default")
      (node (ref "C22") (pin "1") (pinfunction "1_1") (pintype "passive"))
      (node (ref "J2") (pin "4") (pinfunction "4_4") (pintype "passive"))
      (node (ref "J5") (pin "4") (pinfunction "4_4") (pintype "passive"))
      (node (ref "R30") (pin "1") (pinfunction "1_1") (pintype "passive"))
      (node (ref "R35") (pin "1") (pinfunction "1_1") (pintype "passive"))
    )
    (net (code "9") (name "/HALLB") (class "Default")
      (node (ref "C21") (pin "1") (pinfunction "1_1") (pintype "passive"))
      (node (ref "J2") (pin "6") (pinfunction "6_6") (pintype "passive"))
      (node (ref "J5") (pin "3") (pinfunction "3_3") (pintype "passive"))
      (node (ref "R29") (pin "1") (pinfunction "1_1") (pintype "passive"))
      (node (ref "R36") (pin "1") (pinfunction "1_1") (pintype "passive"))
    )
    (net (code "10") (name "/HALLC") (class "Default")
      (node (ref "C20") (pin "1") (pinfunction "1_1") (pintype "passive"))
      (node (ref "J2") (pin "16") (pinfunction "16_16") (pintype "passive"))
      (node (ref "J5") (pin "2") (pinfunction "2_2") (pintype "passive"))
      (node (ref "R28") (pin "1") (pinfunction "1_1") (pintype "passive"))
      (node (ref "R38") (pin "1") (pinfunction "1_1") (pintype "passive"))
    )
    (net (code "11") (name "/IDRIVE") (class "Default")
      (node (ref "J1") (pin "18") (pinfunction "18_18") (pintype "passive"))
      (node (ref "R15") (pin "1") (pinfunction "1_1") (pintype "passive"))
      (node (ref "R4") (pin "1") (pinfunction "1_1") (pintype "passive"))
      (node (ref "R8") (pin "2") (pinfunction "2_2") (pintype "passive"))
      (node (ref "U1") (pin "19") (pinfunction "SDI_19") (pintype "input"))
    )
    (net (code "12") (name "/INHA") (class "Default")
      (node (ref "J2") (pin "1") (pinfunction "1_1") (pintype "passive"))
      (node (ref "U1") (pin "25") (pinfunction "INHA_25") (pintype "input"))
    )
    (net (code "13") (name "/INHB") (class "Default")
      (node (ref "J2") (pin "5") (pinfunction "5_5") (pintype "passive"))
      (node (ref "R36") (pin "2") (pinfunction "2_2") (pintype "passive"))
      (node (ref "U1") (pin "27") (pinfunction "INHB_27") (pintype "input"))
    )
    (net (code "14") (name "/INHC") (class "Default")
      (node (ref "J2") (pin "9") (pinfunction "9_9") (pintype "passive"))
      (node (ref "U1") (pin "29") (pinfunction "INHC_29") (pintype "input"))
    )
    (net (code "15") (name "/INLA") (class "Default")
      (node (ref "J2") (pin "3") (pinfunction "3_3") (pintype "passive"))
      (node (ref "R35") (pin "2") (pinfunction "2_2") (pintype "passive"))
      (node (ref "U1") (pin "26") (pinfunction "INLA_26") (pintype "input"))
    )
    (net (code "16") (name "/INLB") (class "Default")
      (node (ref "J2") (pin "7") (pinfunction "7_7") (pintype "passive"))
      (node (ref "R38") (pin "2") (pinfunction "2_2") (pintype "passive"))
      (node (ref "U1") (pin "28") (pinfunction "INLB_28") (pintype "input"))
    )
    (net (code "17") (name "/INLC") (class "Default")
      (node (ref "J2") (pin "11") (pinfunction "11_11") (pintype "passive"))
      (node (ref "U1") (pin "30") (pinfunction "INLC_30") (pintype "input"))
    )
    (net (code "18") (name "/ISEN") (class "Default")
      (node (ref "C12") (pin "1") (pinfunction "1_1") (pintype "passive"))
      (node (ref "J1") (pin "16") (pinfunction "16_16") (pintype "passive"))
      (node (ref "R12") (pin "1") (pinfunction "1_1") (pintype "passive"))
      (node (ref "U2") (pin "1") (pinfunction "OUT_1") (pintype "output"))
    )
    (net (code "19") (name "/LED") (class "Default")
      (node (ref "D5") (pin "1") (pinfunction "A_1") (pintype "passive"))
      (node (ref "J2") (pin "15") (pinfunction "15_15") (pintype "passive"))
    )
    (net (code "20") (name "/MODE") (class "Default")
      (node (ref "J2") (pin "13") (pinfunction "13_13") (pintype "passive"))
      (node (ref "R14") (pin "2") (pinfunction "2_2") (pintype "passive"))
      (node (ref "R20") (pin "2") (pinfunction "2_2") (pintype "passive"))
    )
    (net (code "21") (name "/MOTA") (class "Default")
      (node (ref "J4") (pin "1") (pinfunction "1_1") (pintype "passive"))
      (node (ref "R1") (pin "2") (pinfunction "2_2") (pintype "passive"))
      (node (ref "TP4") (pin "1") (pintype "passive"))
      (node (ref "U4") (pin "10") (pinfunction "VSW_10") (pintype "passive"))
      (node (ref "U4") (pin "11") (pinfunction "VSW_11") (pintype "passive"))
      (node (ref "U4") (pin "3") (pinfunction "VSW_3") (pintype "passive"))
      (node (ref "U4") (pin "4") (pinfunction "VSW_4") (pintype "passive"))
      (node (ref "U4") (pin "5") (pinfunction "VSW_5") (pintype "passive"))
      (node (ref "U4") (pin "6") (pinfunction "VSW_6") (pintype "passive"))
      (node (ref "U4") (pin "7") (pinfunction "VSW_7") (pintype "passive"))
      (node (ref "U4") (pin "8") (pinfunction "VSW_8") (pintype "passive"))
      (node (ref "U4") (pin "9") (pinfunction "VSW_9") (pintype "passive"))
    )
    (net (code "22") (name "/MOTB") (class "Default")
      (node (ref "J4") (pin "2") (pinfunction "2_2") (pintype "passive"))
      (node (ref "R2") (pin "2") (pinfunction "2_2") (pintype "passive"))
      (node (ref "TP5") (pin "1") (pintype "passive"))
      (node (ref "U5") (pin "10") (pinfunction "VSW_10") (pintype "passive"))
      (node (ref "U5") (pin "11") (pinfunction "VSW_11") (pintype "passive"))
      (node (ref "U5") (pin "3") (pinfunction "VSW_3") (pintype "passive"))
      (node (ref "U5") (pin "4") (pinfunction "VSW_4") (pintype "passive"))
      (node (ref "U5") (pin "5") (pinfunction "VSW_5") (pintype "passive"))
      (node (ref "U5") (pin "6") (pinfunction "VSW_6") (pintype "passive"))
      (node (ref "U5") (pin "7") (pinfunction "VSW_7") (pintype "passive"))
      (node (ref "U5") (pin "8") (pinfunction "VSW_8") (pintype "passive"))
      (node (ref "U5") (pin "9") (pinfunction "VSW_9") (pintype "passive"))
    )
    (net (code "23") (name "/MOTC") (class "Default")
      (node (ref "J4") (pin "3") (pinfunction "3_3") (pintype "passive"))
      (node (ref "R3") (pin "2") (pinfunction "2_2") (pintype "passive"))
      (node (ref "TP6") (pin "1") (pintype "passive"))
      (node (ref "U6") (pin "10") (pinfunction "VSW_10") (pintype "passive"))
      (node (ref "U6") (pin "11") (pinfunction "VSW_11") (pintype "passive"))
      (node (ref "U6") (pin "3") (pinfunction "VSW_3") (pintype "passive"))
      (node (ref "U6") (pin "4") (pinfunction "VSW_4") (pintype "passive"))
      (node (ref "U6") (pin "5") (pinfunction "VSW_5") (pintype "passive"))
      (node (ref "U6") (pin "6") (pinfunction "VSW_6") (pintype "passive"))
      (node (ref "U6") (pin "7") (pinfunction "VSW_7") (pintype "passive"))
      (node (ref "U6") (pin "8") (pinfunction "VSW_8") (pintype "passive"))
      (node (ref "U6") (pin "9") (pinfunction "VSW_9") (pintype "passive"))
    )
    (net (code "24") (name "/POT") (class "Default")
      (node (ref "J1") (pin "11") (pinfunction "11_11") (pintype "passive"))
      (node (ref "R34") (pin "2") (pinfunction "WIPER_2") (pintype "passive"))
    )
    (net (code "25") (name "/SCLK") (class "Default")
      (node (ref "J1") (pin "13") (pinfunction "13_13") (pintype "passive"))
      (node (ref "R17") (pin "2") (pinfunction "2_2") (pintype "passive"))
    )
    (net (code "26") (name "/SDI") (class "Default")
      (node (ref "J2") (pin "12") (pinfunction "12_12") (pintype "passive"))
      (node (ref "R15") (pin "2") (pinfunction "2_2") (pintype "passive"))
    )
    (net (code "27") (name "/SDO") (class "Default")
      (node (ref "J2") (pin "14") (pinfunction "14_14") (pintype "passive"))
      (node (ref "R13") (pin "2") (pinfunction "2_2") (pintype "passive"))
    )
    (net (code "28") (name "/SHA") (class "Default")
      (node (ref "NT2") (pin "2") (pinfunction "2_2") (pintype "passive"))
      (node (ref "U1") (pin "6") (pinfunction "SHA_6") (pintype "input"))
    )
    (net (code "29") (name "/SHB") (class "Default")
      (node (ref "NT3") (pin "2") (pinfunction "2_2") (pintype "passive"))
      (node (ref "U1") (pin "11") (pinfunction "SHB_11") (pintype "input"))
    )
    (net (code "30") (name "/SHC") (class "Default")
      (node (ref "NT4") (pin "2") (pinfunction "2_2") (pintype "passive"))
      (node (ref "U1") (pin "14") (pinfunction "SHC_14") (pintype "input"))
    )
    (net (code "31") (name "/SL") (class "Default")
      (node (ref "C13") (pin "1") (pinfunction "1_1") (pintype "passive"))
      (node (ref "NT5") (pin "2") (pinfunction "2_2") (pintype "passive"))
      (node (ref "U1") (pin "16") (pinfunction "SLC_16") (pintype "input"))
      (node (ref "U1") (pin "8") (pinfunction "SLA_8") (pintype "input"))
      (node (ref "U1") (pin "9") (pinfunction "SLB_9") (pintype "input"))
      (node (ref "U2") (pin "3") (pinfunction "IN+_3") (pintype "input"))
    )
    (net (code "32") (name "/SP") (class "Default")
      (node (ref "C4") (pin "2") (pinfunction "2_2") (pintype "passive"))
      (node (ref "C5") (pin "2") (pinfunction "2_2") (pintype "passive"))
      (node (ref "C6") (pin "2") (pinfunction "2_2") (pintype "passive"))
      (node (ref "NT5") (pin "1") (pinfunction "1_1") (pintype "passive"))
      (node (ref "R21") (pin "2") (pinfunction "2_2") (pintype "passive"))
      (node (ref "U4") (pin "12") (pinfunction "PGND_12") (pintype "power_in"))
      (node (ref "U4") (pin "13") (pinfunction "PGND_13") (pintype "power_in"))
      (node (ref "U4") (pin "14") (pinfunction "PGND_14") (pintype "power_in"))
      (node (ref "U4") (pin "15") (pinfunction "PGND_15") (pintype "power_in"))
      (node (ref "U4") (pin "16") (pinfunction "PGND_16") (pintype "power_in"))
      (node (ref "U4") (pin "17") (pinfunction "PGND_17") (pintype "power_in"))
      (node (ref "U4") (pin "18") (pinfunction "PGND_18") (pintype "power_in"))
      (node (ref "U4") (pin "19") (pinfunction "PGND_19") (pintype "power_in"))
      (node (ref "U4") (pin "20") (pinfunction "PGND_20") (pintype "power_in"))
      (node (ref "U5") (pin "12") (pinfunction "PGND_12") (pintype "power_in"))
      (node (ref "U5") (pin "13") (pinfunction "PGND_13") (pintype "power_in"))
      (node (ref "U5") (pin "14") (pinfunction "PGND_14") (pintype "power_in"))
      (node (ref "U5") (pin "15") (pinfunction "PGND_15") (pintype "power_in"))
      (node (ref "U5") (pin "16") (pinfunction "PGND_16") (pintype "power_in"))
      (node (ref "U5") (pin "17") (pinfunction "PGND_17") (pintype "power_in"))
      (node (ref "U5") (pin "18") (pinfunction "PGND_18") (pintype "power_in"))
      (node (ref "U5") (pin "19") (pinfunction "PGND_19") (pintype "power_in"))
      (node (ref "U5") (pin "20") (pinfunction "PGND_20") (pintype "power_in"))
      (node (ref "U6") (pin "12") (pinfunction "PGND_12") (pintype "power_in"))
      (node (ref "U6") (pin "13") (pinfunction "PGND_13") (pintype "power_in"))
      (node (ref "U6") (pin "14") (pinfunction "PGND_14") (pintype "power_in"))
      (node (ref "U6") (pin "15") (pinfunction "PGND_15") (pintype "power_in"))
      (node (ref "U6") (pin "16") (pinfunction "PGND_16") (pintype "power_in"))
      (node (ref "U6") (pin "17") (pinfunction "PGND_17") (pintype "power_in"))
      (node (ref "U6") (pin "18") (pinfunction "PGND_18") (pintype "power_in"))
      (node (ref "U6") (pin "19") (pinfunction "PGND_19") (pintype "power_in"))
      (node (ref "U6") (pin "20") (pinfunction "PGND_20") (pintype "power_in"))
    )
    (net (code "33") (name "/VDRAIN") (class "Default")
      (node (ref "NT1") (pin "1") (pinfunction "1_1") (pintype "passive"))
      (node (ref "U1") (pin "4") (pinfunction "VDRAIN_4") (pintype "input"))
    )
    (net (code "34") (name "/VDS") (class "Default")
      (node (ref "J1") (pin "20") (pinfunction "20_20") (pintype "passive"))
      (node (ref "R16") (pin "1") (pinfunction "1_1") (pintype "passive"))
      (node (ref "R17") (pin "1") (pinfunction "1_1") (pintype "passive"))
      (node (ref "R18") (pin "2") (pinfunction "2_2") (pintype "passive"))
      (node (ref "U1") (pin "20") (pinfunction "SCLK_20") (pintype "input"))
    )
    (net (code "35") (name "/VSENA") (class "Default")
      (node (ref "C9") (pin "1") (pinfunction "1_1") (pintype "passive"))
      (node (ref "D2") (pin "1") (pinfunction "D1+_1") (pintype "passive"))
      (node (ref "J1") (pin "6") (pinfunction "6_6") (pintype "passive"))
      (node (ref "R1") (pin "1") (pinfunction "1_1") (pintype "passive"))
      (node (ref "R5") (pin "2") (pinfunction "2_2") (pintype "passive"))
    )
    (net (code "36") (name "/VSENB") (class "Default")
      (node (ref "C10") (pin "1") (pinfunction "1_1") (pintype "passive"))
      (node (ref "D2") (pin "3") (pinfunction "D2+_3") (pintype "passive"))
      (node (ref "J1") (pin "8") (pinfunction "8_8") (pintype "passive"))
      (node (ref "R2") (pin "1") (pinfunction "1_1") (pintype "passive"))
      (node (ref "R6") (pin "2") (pinfunction "2_2") (pintype "passive"))
    )
    (net (code "37") (name "/VSENC") (class "Default")
      (node (ref "C11") (pin "1") (pinfunction "1_1") (pintype "passive"))
      (node (ref "D2") (pin "4") (pinfunction "D2-_4") (pintype "passive"))
      (node (ref "J1") (pin "10") (pinfunction "10_10") (pintype "passive"))
      (node (ref "R3") (pin "1") (pinfunction "1_1") (pintype "passive"))
      (node (ref "R7") (pin "2") (pinfunction "2_2") (pintype "passive"))
    )
    (net (code "38") (name "/VSENVM") (class "Default")
      (node (ref "C19") (pin "1") (pinfunction "1_1") (pintype "passive"))
      (node (ref "D2") (pin "6") (pinfunction "D1-_6") (pintype "passive"))
      (node (ref "J1") (pin "3") (pinfunction "3_3") (pintype "passive"))
      (node (ref "R33") (pin "1") (pinfunction "1_1") (pintype "passive"))
      (node (ref "R37") (pin "2") (pinfunction "2_2") (pintype "passive"))
    )
    (net (code "39") (name "/nFAULT") (class "Default")
      (node (ref "J1") (pin "15") (pinfunction "15_15") (pintype "passive"))
      (node (ref "R10") (pin "1") (pinfunction "1_1") (pintype "passive"))
      (node (ref "R9") (pin "1") (pinfunction "1_1") (pintype "passive"))
      (node (ref "U1") (pin "17") (pinfunction "FAULT_17") (pintype "open_collector"))
    )
    (net (code "40") (name "/nSCS{slash}GAIN") (class "Default")
      (node (ref "J2") (pin "18") (pinfunction "18_18") (pintype "passive"))
      (node (ref "R19") (pin "2") (pinfunction "2_2") (pintype "passive"))
      (node (ref "U1") (pin "21") (pinfunction "SCS_21") (pintype "passive"))
    )
    (net (code "41") (name "3.3V") (class "Default")
      (node (ref "C16") (pin "1") (pinfunction "1_1") (pintype "passive"))
      (node (ref "D1") (pin "2") (pinfunction "A_2") (pintype "passive"))
      (node (ref "D2") (pin "5") (pinfunction "VCC_5") (pintype "power_in"))
      (node (ref "D3") (pin "1") (pinfunction "A_1") (pintype "passive"))
      (node (ref "J1") (pin "1") (pinfunction "1_1") (pintype "passive"))
      (node (ref "J5") (pin "5") (pinfunction "5_5") (pintype "passive"))
      (node (ref "L1") (pin "2") (pinfunction "2_2") (pintype "passive"))
      (node (ref "R11") (pin "2") (pinfunction "2_2") (pintype "passive"))
      (node (ref "R16") (pin "2") (pinfunction "2_2") (pintype "passive"))
      (node (ref "R23") (pin "2") (pinfunction "2_2") (pintype "passive"))
      (node (ref "R24") (pin "2") (pinfunction "2_2") (pintype "passive"))
      (node (ref "R27") (pin "2") (pinfunction "2_2") (pintype "passive"))
      (node (ref "R28") (pin "2") (pinfunction "2_2") (pintype "passive"))
      (node (ref "R29") (pin "2") (pinfunction "2_2") (pintype "passive"))
      (node (ref "R30") (pin "2") (pinfunction "2_2") (pintype "passive"))
      (node (ref "R34") (pin "3") (pinfunction "CW_3") (pintype "passive"))
      (node (ref "R4") (pin "2") (pinfunction "2_2") (pintype "passive"))
      (node (ref "R9") (pin "2") (pinfunction "2_2") (pintype "passive"))
      (node (ref "U2") (pin "5") (pinfunction "V+_5") (pintype "power_in"))
    )
    (net (code "42") (name "GND") (class "Default")
      (node (ref "C1") (pin "2") (pinfunction "2_2") (pintype "passive"))
      (node (ref "C10") (pin "2") (pinfunction "2_2") (pintype "passive"))
      (node (ref "C11") (pin "2") (pinfunction "2_2") (pintype "passive"))
      (node (ref "C13") (pin "2") (pinfunction "2_2") (pintype "passive"))
      (node (ref "C15") (pin "2") (pinfunction "2_2") (pintype "passive"))
      (node (ref "C16") (pin "2") (pinfunction "2_2") (pintype "passive"))
      (node (ref "C17") (pin "2") (pinfunction "-_2") (pintype "passive"))
      (node (ref "C18") (pin "2") (pinfunction "-_2") (pintype "passive"))
      (node (ref "C19") (pin "2") (pinfunction "2_2") (pintype "passive"))
      (node (ref "C2") (pin "2") (pinfunction "2_2") (pintype "passive"))
      (node (ref "C20") (pin "2") (pinfunction "2_2") (pintype "passive"))
      (node (ref "C21") (pin "2") (pinfunction "2_2") (pintype "passive"))
      (node (ref "C22") (pin "2") (pinfunction "2_2") (pintype "passive"))
      (node (ref "C8") (pin "2") (pinfunction "2_2") (pintype "passive"))
      (node (ref "C9") (pin "2") (pinfunction "2_2") (pintype "passive"))
      (node (ref "D2") (pin "2") (pinfunction "GND_2") (pintype "power_in"))
      (node (ref "D4") (pin "2") (pinfunction "A_2") (pintype "passive"))
      (node (ref "J1") (pin "4") (pinfunction "4_4") (pintype "passive"))
      (node (ref "J2") (pin "2") (pinfunction "2_2") (pintype "passive"))
      (node (ref "J3") (pin "2") (pinfunction "2_2") (pintype "passive"))
      (node (ref "J5") (pin "1") (pinfunction "1_1") (pintype "passive"))
      (node (ref "R18") (pin "1") (pinfunction "1_1") (pintype "passive"))
      (node (ref "R19") (pin "1") (pinfunction "1_1") (pintype "passive"))
      (node (ref "R20") (pin "1") (pinfunction "1_1") (pintype "passive"))
      (node (ref "R21") (pin "1") (pinfunction "1_1") (pintype "passive"))
      (node (ref "R22") (pin "1") (pinfunction "1_1") (pintype "passive"))
      (node (ref "R25") (pin "1") (pinfunction "1_1") (pintype "passive"))
      (node (ref "R26") (pin "1") (pinfunction "1_1") (pintype "passive"))
      (node (ref "R31") (pin "1") (pinfunction "1_1") (pintype "passive"))
      (node (ref "R32") (pin "1") (pinfunction "1_1") (pintype "passive"))
      (node (ref "R34") (pin "1") (pinfunction "CCW_1") (pintype "passive"))
      (node (ref "R37") (pin "1") (pinfunction "1_1") (pintype "passive"))
      (node (ref "R39") (pin "1") (pinfunction "1_1") (pintype "passive"))
      (node (ref "R5") (pin "1") (pinfunction "1_1") (pintype "passive"))
      (node (ref "R6") (pin "1") (pinfunction "1_1") (pintype "passive"))
      (node (ref "R7") (pin "1") (pinfunction "1_1") (pintype "passive"))
      (node (ref "R8") (pin "1") (pinfunction "1_1") (pintype "passive"))
      (node (ref "TP10") (pin "1") (pinfunction "1_1") (pintype "passive"))
      (node (ref "TP10") (pin "2") (pinfunction "2_2") (pintype "passive"))
      (node (ref "U1") (pin "23") (pinfunction "AGND_23") (pintype "power_in"))
      (node (ref "U1") (pin "31") (pinfunction "PGND_31") (pintype "power_in"))
      (node (ref "U1") (pin "33") (pinfunction "PAD_33") (pintype "power_in"))
      (node (ref "U2") (pin "2") (pinfunction "V-_2") (pintype "power_in"))
      (node (ref "U3") (pin "2") (pinfunction "GND_2") (pintype "power_in"))
    )
    (net (code "43") (name "Net-(D1-K)") (class "Default")
      (node (ref "D1") (pin "1") (pinfunction "K_1") (pintype "passive"))
      (node (ref "R10") (pin "2") (pinfunction "2_2") (pintype "passive"))
    )
    (net (code "44") (name "Net-(D3-K)") (class "Default")
      (node (ref "D3") (pin "2") (pinfunction "K_2") (pintype "passive"))
      (node (ref "R32") (pin "2") (pinfunction "2_2") (pintype "passive"))
    )
    (net (code "45") (name "Net-(D4-K)") (class "Default")
      (node (ref "C14") (pin "2") (pinfunction "2_2") (pintype "passive"))
      (node (ref "D4") (pin "1") (pinfunction "K_1") (pintype "passive"))
      (node (ref "L1") (pin "1") (pinfunction "1_1") (pintype "passive"))
      (node (ref "U3") (pin "6") (pinfunction "SW_6") (pintype "power_in"))
    )
    (net (code "46") (name "Net-(D5-K)") (class "Default")
      (node (ref "D5") (pin "2") (pinfunction "K_2") (pintype "passive"))
      (node (ref "R39") (pin "2") (pinfunction "2_2") (pintype "passive"))
    )
    (net (code "47") (name "Net-(J2-Pad17)") (class "Default")
      (node (ref "J2") (pin "17") (pinfunction "17_17") (pintype "passive"))
      (node (ref "R23") (pin "1") (pinfunction "1_1") (pintype "passive"))
      (node (ref "R25") (pin "2") (pinfunction "2_2") (pintype "passive"))
    )
    (net (code "48") (name "Net-(J2-Pad19)") (class "Default")
      (node (ref "J2") (pin "19") (pinfunction "19_19") (pintype "passive"))
      (node (ref "R24") (pin "1") (pinfunction "1_1") (pintype "passive"))
      (node (ref "R26") (pin "2") (pinfunction "2_2") (pintype "passive"))
    )
    (net (code "49") (name "Net-(U1-CPH)") (class "Default")
      (node (ref "C7") (pin "1") (pinfunction "1_1") (pintype "passive"))
      (node (ref "U1") (pin "1") (pinfunction "CPH_1") (pintype "passive"))
    )
    (net (code "50") (name "Net-(U1-CPL)") (class "Default")
      (node (ref "C7") (pin "2") (pinfunction "2_2") (pintype "passive"))
      (node (ref "U1") (pin "32") (pinfunction "CPL_32") (pintype "passive"))
    )
    (net (code "51") (name "Net-(U1-DVDD)") (class "Default")
      (node (ref "C8") (pin "1") (pinfunction "1_1") (pintype "passive"))
      (node (ref "U1") (pin "24") (pinfunction "DVDD_24") (pintype "power_in"))
    )
    (net (code "52") (name "Net-(U1-SDO)") (class "Default")
      (node (ref "R11") (pin "1") (pinfunction "1_1") (pintype "passive"))
      (node (ref "R13") (pin "1") (pinfunction "1_1") (pintype "passive"))
      (node (ref "R14") (pin "1") (pinfunction "1_1") (pintype "passive"))
      (node (ref "U1") (pin "18") (pinfunction "SDO_18") (pintype "passive"))
    )
    (net (code "53") (name "Net-(U1-VCP)") (class "Default")
      (node (ref "C3") (pin "2") (pinfunction "2_2") (pintype "passive"))
      (node (ref "U1") (pin "2") (pinfunction "VCP_2") (pintype "power_in"))
    )
    (net (code "54") (name "Net-(U2-IN-)") (class "Default")
      (node (ref "C12") (pin "2") (pinfunction "2_2") (pintype "passive"))
      (node (ref "R12") (pin "2") (pinfunction "2_2") (pintype "passive"))
      (node (ref "R22") (pin "2") (pinfunction "2_2") (pintype "passive"))
      (node (ref "U2") (pin "4") (pinfunction "IN-_4") (pintype "input"))
    )
    (net (code "55") (name "Net-(U3-CB)") (class "Default")
      (node (ref "C14") (pin "1") (pinfunction "1_1") (pintype "passive"))
      (node (ref "U3") (pin "1") (pinfunction "CB_1") (pintype "output"))
    )
    (net (code "56") (name "Net-(U3-FB)") (class "Default")
      (node (ref "R27") (pin "1") (pinfunction "1_1") (pintype "passive"))
      (node (ref "R31") (pin "2") (pinfunction "2_2") (pintype "passive"))
      (node (ref "U3") (pin "3") (pinfunction "FB_3") (pintype "input"))
    )
    (net (code "57") (name "Net-(U4-SH)") (class "Default")
      (node (ref "NT2") (pin "1") (pinfunction "1_1") (pintype "passive"))
      (node (ref "U4") (pin "2") (pinfunction "SH_2") (pintype "passive"))
    )
    (net (code "58") (name "Net-(U5-SH)") (class "Default")
      (node (ref "NT3") (pin "1") (pinfunction "1_1") (pintype "passive"))
      (node (ref "U5") (pin "2") (pinfunction "SH_2") (pintype "passive"))
    )
    (net (code "59") (name "Net-(U6-SH)") (class "Default")
      (node (ref "NT4") (pin "1") (pinfunction "1_1") (pintype "passive"))
      (node (ref "U6") (pin "2") (pinfunction "SH_2") (pintype "passive"))
    )
    (net (code "60") (name "VM") (class "Default")
      (node (ref "C1") (pin "1") (pinfunction "1_1") (pintype "passive"))
      (node (ref "C15") (pin "1") (pinfunction "1_1") (pintype "passive"))
      (node (ref "C17") (pin "1") (pinfunction "+_1") (pintype "passive"))
      (node (ref "C18") (pin "1") (pinfunction "+_1") (pintype "passive"))
      (node (ref "C2") (pin "1") (pinfunction "1_1") (pintype "passive"))
      (node (ref "C3") (pin "1") (pinfunction "1_1") (pintype "passive"))
      (node (ref "C4") (pin "1") (pinfunction "1_1") (pintype "passive"))
      (node (ref "C5") (pin "1") (pinfunction "1_1") (pintype "passive"))
      (node (ref "C6") (pin "1") (pinfunction "1_1") (pintype "passive"))
      (node (ref "J3") (pin "1") (pinfunction "1_1") (pintype "passive"))
      (node (ref "NT1") (pin "2") (pinfunction "2_2") (pintype "passive"))
      (node (ref "R33") (pin "2") (pinfunction "2_2") (pintype "passive"))
      (node (ref "U1") (pin "3") (pinfunction "VM_3") (pintype "power_in"))
      (node (ref "U3") (pin "5") (pinfunction "VIN_5") (pintype "power_in"))
      (node (ref "U4") (pin "27") (pinfunction "VIN_27") (pintype "power_in"))
      (node (ref "U5") (pin "27") (pinfunction "VIN_27") (pintype "power_in"))
      (node (ref "U6") (pin "27") (pinfunction "VIN_27") (pintype "power_in"))
    )
    (net (code "61") (name "unconnected-(J1-Pad2)") (class "Default")
      (node (ref "J1") (pin "2") (pinfunction "2_2") (pintype "passive+no_connect"))
    )
    (net (code "62") (name "unconnected-(J1-Pad5)") (class "Default")
      (node (ref "J1") (pin "5") (pinfunction "5_5") (pintype "passive+no_connect"))
    )
    (net (code "63") (name "unconnected-(J1-Pad7)") (class "Default")
      (node (ref "J1") (pin "7") (pinfunction "7_7") (pintype "passive+no_connect"))
    )
    (net (code "64") (name "unconnected-(J1-Pad12)") (class "Default")
      (node (ref "J1") (pin "12") (pinfunction "12_12") (pintype "passive+no_connect"))
    )
    (net (code "65") (name "unconnected-(J1-Pad14)") (class "Default")
      (node (ref "J1") (pin "14") (pinfunction "14_14") (pintype "passive+no_connect"))
    )
    (net (code "66") (name "unconnected-(J1-Pad17)") (class "Default")
      (node (ref "J1") (pin "17") (pinfunction "17_17") (pintype "passive+no_connect"))
    )
    (net (code "67") (name "unconnected-(J1-Pad19)") (class "Default")
      (node (ref "J1") (pin "19") (pinfunction "19_19") (pintype "passive+no_connect"))
    )
    (net (code "68") (name "unconnected-(J2-Pad8)") (class "Default")
      (node (ref "J2") (pin "8") (pinfunction "8_8") (pintype "passive+no_connect"))
    )
    (net (code "69") (name "unconnected-(J2-Pad10)") (class "Default")
      (node (ref "J2") (pin "10") (pinfunction "10_10") (pintype "passive+no_connect"))
    )
    (net (code "70") (name "unconnected-(J2-Pad20)") (class "Default")
      (node (ref "J2") (pin "20") (pinfunction "20_20") (pintype "passive+no_connect"))
    )
    (net (code "71") (name "unconnected-(U3-SHDN-Pad4)") (class "Default")
      (node (ref "U3") (pin "4") (pinfunction "SHDN_4") (pintype "input+no_connect"))
    )
    (net (code "72") (name "unconnected-(U4-NC-Pad21)") (class "Default")
      (node (ref "U4") (pin "21") (pinfunction "NC_21") (pintype "passive+no_connect"))
    )
    (net (code "73") (name "unconnected-(U4-NC-Pad23)") (class "Default")
      (node (ref "U4") (pin "23") (pinfunction "NC_23") (pintype "passive+no_connect"))
    )
    (net (code "74") (name "unconnected-(U4-NC-Pad24)") (class "Default")
      (node (ref "U4") (pin "24") (pinfunction "NC_24") (pintype "passive+no_connect"))
    )
    (net (code "75") (name "unconnected-(U4-NC-Pad25)") (class "Default")
      (node (ref "U4") (pin "25") (pinfunction "NC_25") (pintype "passive+no_connect"))
    )
    (net (code "76") (name "unconnected-(U4-NC-Pad26)") (class "Default")
      (node (ref "U4") (pin "26") (pinfunction "NC_26") (pintype "passive+no_connect"))
    )
    (net (code "77") (name "unconnected-(U5-NC-Pad21)") (class "Default")
      (node (ref "U5") (pin "21") (pinfunction "NC_21") (pintype "passive+no_connect"))
    )
    (net (code "78") (name "unconnected-(U5-NC-Pad23)") (class "Default")
      (node (ref "U5") (pin "23") (pinfunction "NC_23") (pintype "passive+no_connect"))
    )
    (net (code "79") (name "unconnected-(U5-NC-Pad24)") (class "Default")
      (node (ref "U5") (pin "24") (pinfunction "NC_24") (pintype "passive+no_connect"))
    )
    (net (code "80") (name "unconnected-(U5-NC-Pad25)") (class "Default")
      (node (ref "U5") (pin "25") (pinfunction "NC_25") (pintype "passive+no_connect"))
    )
    (net (code "81") (name "unconnected-(U5-NC-Pad26)") (class "Default")
      (node (ref "U5") (pin "26") (pinfunction "NC_26") (pintype "passive+no_connect"))
    )
    (net (code "82") (name "unconnected-(U6-NC-Pad21)") (class "Default")
      (node (ref "U6") (pin "21") (pinfunction "NC_21") (pintype "passive+no_connect"))
    )
    (net (code "83") (name "unconnected-(U6-NC-Pad23)") (class "Default")
      (node (ref "U6") (pin "23") (pinfunction "NC_23") (pintype "passive+no_connect"))
    )
    (net (code "84") (name "unconnected-(U6-NC-Pad24)") (class "Default")
      (node (ref "U6") (pin "24") (pinfunction "NC_24") (pintype "passive+no_connect"))
    )
    (net (code "85") (name "unconnected-(U6-NC-Pad25)") (class "Default")
      (node (ref "U6") (pin "25") (pinfunction "NC_25") (pintype "passive+no_connect"))
    )
    (net (code "86") (name "unconnected-(U6-NC-Pad26)") (class "Default")
      (node (ref "U6") (pin "26") (pinfunction "NC_26") (pintype "passive+no_connect"))
    )
  )
)
